# generic_midi_2.net
KiCad netlist of a schematic drawn in EAGLE
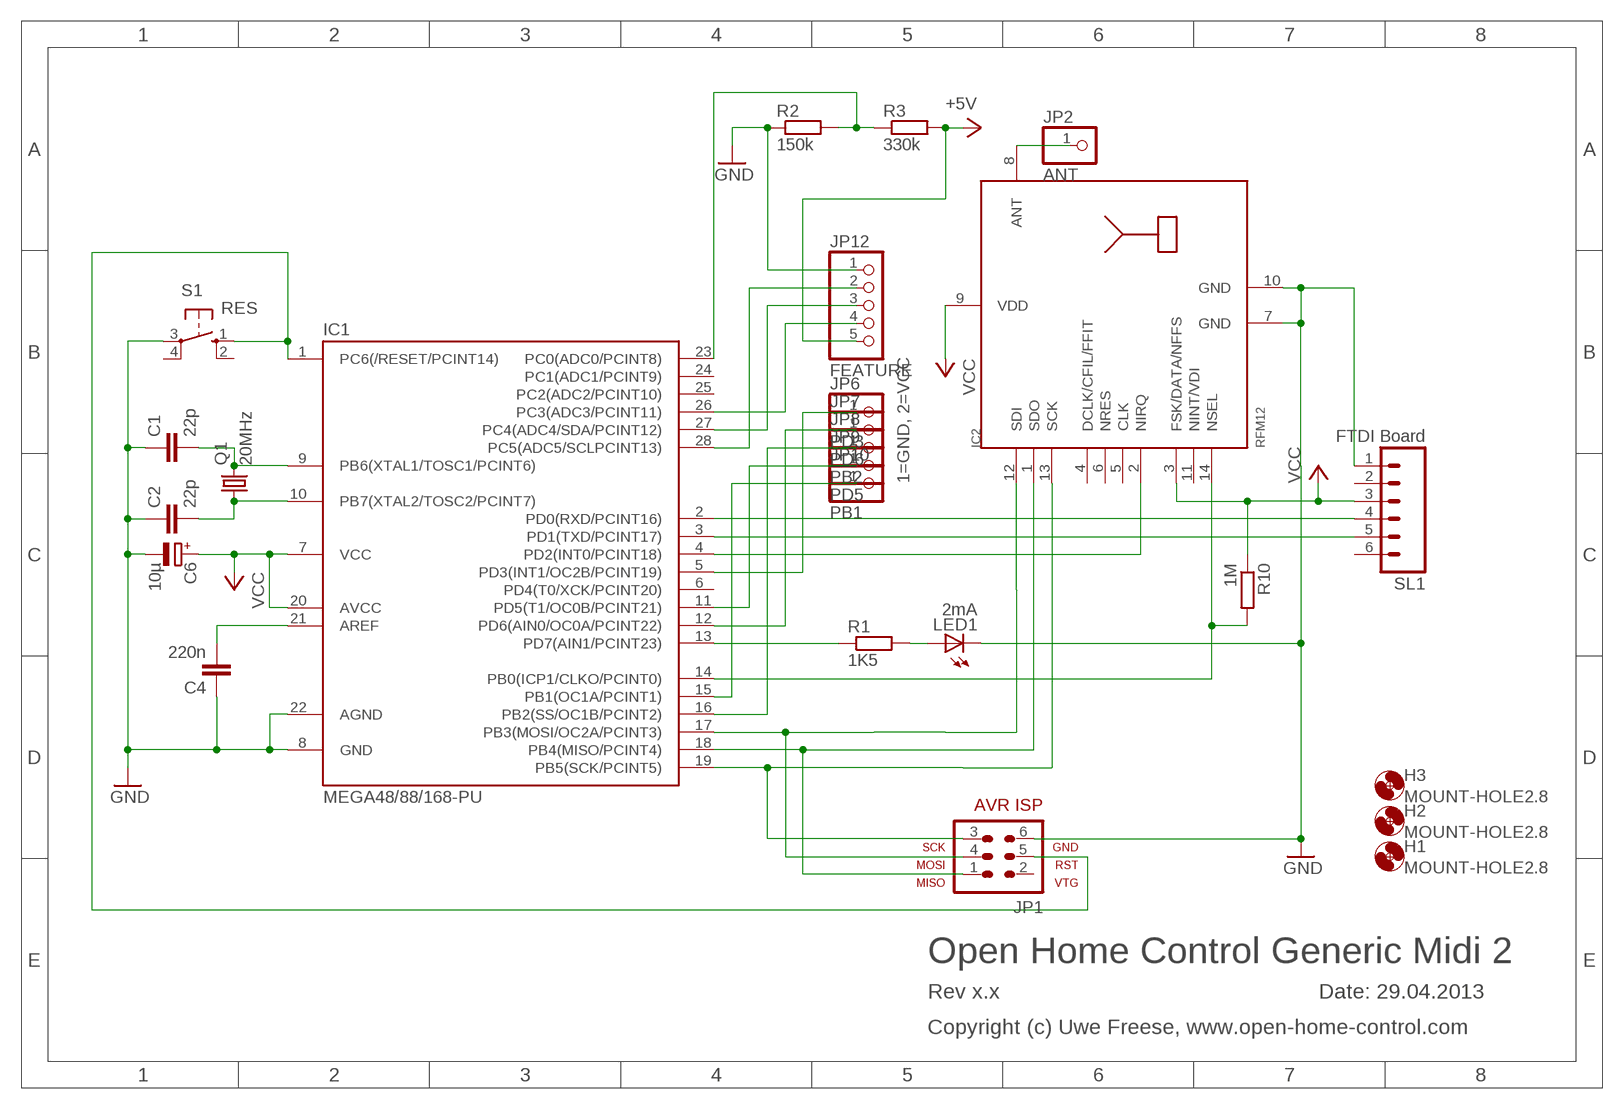
[diagram p0: schematic, sheet 1]

(export (version "E")
  (design (tool "Eeschema 10.0.6"))
  (components
    (comp (ref "C1")
      (value "22p")
      (footprint "eagle-import:C025-024X044")
      (libsource (lib "eagle-import") (part "C-EU025-024X044"))
    )
    (comp (ref "C2")
      (value "22p")
      (footprint "eagle-import:C025-024X044")
      (libsource (lib "eagle-import") (part "C-EU025-024X044"))
    )
    (comp (ref "C4")
      (value "220n")
      (footprint "eagle-import:C025-030X050")
      (libsource (lib "eagle-import") (part "C-EU025-030X050"))
    )
    (comp (ref "C6")
      (value "10µ")
      (footprint "eagle-import:E1,8-4")
      (libsource (lib "eagle-import") (part "CPOL-EUE1.8-4"))
    )
    (comp (ref "H1")
      (value "MOUNT-HOLE2.8")
      (footprint "eagle-import:2,8")
      (libsource (lib "eagle-import") (part "MOUNT-HOLE2.8"))
    )
    (comp (ref "H2")
      (value "MOUNT-HOLE2.8")
      (footprint "eagle-import:2,8")
      (libsource (lib "eagle-import") (part "MOUNT-HOLE2.8"))
    )
    (comp (ref "H3")
      (value "MOUNT-HOLE2.8")
      (footprint "eagle-import:2,8")
      (libsource (lib "eagle-import") (part "MOUNT-HOLE2.8"))
    )
    (comp (ref "IC1")
      (value "MEGA48/88/168-PU")
      (footprint "eagle-import:DIL28-3")
      (libsource (lib "eagle-import") (part "MEGA48/88/168-PU"))
    )
    (comp (ref "IC2")
      (value "RFM12")
      (footprint "eagle-import:RFM")
      (libsource (lib "eagle-import") (part "RFM12"))
    )
    (comp (ref "JP1")
      (value "AVR-ISP-6")
      (footprint "eagle-import:AVR-ISP-6")
      (libsource (lib "eagle-import") (part "AVR-ISP-6"))
    )
    (comp (ref "JP2")
      (value "ANT")
      (footprint "eagle-import:1X01")
      (libsource (lib "eagle-import") (part "PINHD-1X1"))
    )
    (comp (ref "JP6")
      (value "PD3")
      (footprint "eagle-import:1X01")
      (libsource (lib "eagle-import") (part "PINHD-1X1"))
    )
    (comp (ref "JP7")
      (value "PD6")
      (footprint "eagle-import:1X01")
      (libsource (lib "eagle-import") (part "PINHD-1X1"))
    )
    (comp (ref "JP8")
      (value "PB2")
      (footprint "eagle-import:1X01")
      (libsource (lib "eagle-import") (part "PINHD-1X1"))
    )
    (comp (ref "JP9")
      (value "PD5")
      (footprint "eagle-import:1X01")
      (libsource (lib "eagle-import") (part "PINHD-1X1"))
    )
    (comp (ref "JP10")
      (value "PB1")
      (footprint "eagle-import:1X01")
      (libsource (lib "eagle-import") (part "PINHD-1X1"))
    )
    (comp (ref "JP12")
      (value "FEATURE")
      (footprint "eagle-import:1X05")
      (libsource (lib "eagle-import") (part "PINHD-1X5"))
    )
    (comp (ref "LED1")
      (value "2mA")
      (footprint "eagle-import:LED3MM")
      (libsource (lib "eagle-import") (part "LED3MM"))
    )
    (comp (ref "Q1")
      (value "20MHz")
      (footprint "eagle-import:HC49_S")
      (libsource (lib "eagle-import") (part "CRYSTALHC49S"))
    )
    (comp (ref "R1")
      (value "1K5")
      (footprint "eagle-import:0207_7")
      (libsource (lib "eagle-import") (part "R-EU_0207/7"))
    )
    (comp (ref "R2")
      (value "150k")
      (footprint "eagle-import:0207_7")
      (libsource (lib "eagle-import") (part "R-EU_0207/7"))
    )
    (comp (ref "R3")
      (value "330k")
      (footprint "eagle-import:0207_7")
      (libsource (lib "eagle-import") (part "R-EU_0207/7"))
    )
    (comp (ref "R10")
      (value "1M")
      (footprint "eagle-import:0207_7")
      (libsource (lib "eagle-import") (part "R-EU_0207/7"))
    )
    (comp (ref "S1")
      (value "RES")
      (footprint "eagle-import:B3F-10XX")
      (fields (field (name "MPN") "B3F-1000"))
      (libsource (lib "eagle-import") (part "10-XX"))
    )
    (comp (ref "SL1")
      (value "FTDI Board")
      (footprint "eagle-import:06P")
      (libsource (lib "eagle-import") (part "M06"))
    )
  )
  (nets
    (net (code "1") (name "+5V") (class "Default")
      (node (ref "JP12") (pin "5") (pinfunction "5_5") (pintype "passive"))
      (node (ref "R3") (pin "2") (pinfunction "2_2") (pintype "passive"))
    )
    (net (code "2") (name "GND") (class "Default")
      (node (ref "C1") (pin "1") (pinfunction "1_1") (pintype "passive"))
      (node (ref "C2") (pin "1") (pinfunction "1_1") (pintype "passive"))
      (node (ref "C4") (pin "1") (pinfunction "1_1") (pintype "passive"))
      (node (ref "C6") (pin "-") (pinfunction "-_-") (pintype "passive"))
      (node (ref "IC1") (pin "22") (pinfunction "AGND_22") (pintype "power_in"))
      (node (ref "IC1") (pin "8") (pinfunction "GND_8") (pintype "power_in"))
      (node (ref "IC2") (pin "10") (pinfunction "GND_10") (pintype "power_in"))
      (node (ref "IC2") (pin "7") (pinfunction "GND_7") (pintype "power_in"))
      (node (ref "JP1") (pin "6") (pinfunction "6_6") (pintype "passive"))
      (node (ref "JP12") (pin "1") (pinfunction "1_1") (pintype "passive"))
      (node (ref "LED1") (pin "K") (pinfunction "C_K") (pintype "passive"))
      (node (ref "R2") (pin "1") (pinfunction "1_1") (pintype "passive"))
      (node (ref "S1") (pin "3") (pinfunction "P_3") (pintype "passive"))
      (node (ref "SL1") (pin "1") (pinfunction "1_1") (pintype "passive"))
    )
    (net (code "3") (name "Net-(IC1-AREF)") (class "Default")
      (node (ref "C4") (pin "2") (pinfunction "2_2") (pintype "passive"))
      (node (ref "IC1") (pin "21") (pinfunction "AREF_21") (pintype "passive"))
    )
    (net (code "4") (name "Net-(IC1-PB0(ICP1{slash}CLKO{slash}PCINT0))") (class "Default")
      (node (ref "IC1") (pin "14") (pinfunction "PB0(ICP1/CLKO/PCINT0)_14") (pintype "bidirectional"))
      (node (ref "IC2") (pin "14") (pinfunction "NSEL_14") (pintype "bidirectional"))
      (node (ref "R10") (pin "2") (pinfunction "2_2") (pintype "passive"))
    )
    (net (code "5") (name "Net-(IC1-PB1(OC1A{slash}PCINT1))") (class "Default")
      (node (ref "IC1") (pin "15") (pinfunction "PB1(OC1A/PCINT1)_15") (pintype "bidirectional"))
      (node (ref "JP10") (pin "1") (pinfunction "1_1") (pintype "passive"))
    )
    (net (code "6") (name "Net-(IC1-PB2(SS{slash}OC1B{slash}PCINT2))") (class "Default")
      (node (ref "IC1") (pin "16") (pinfunction "PB2(SS/OC1B/PCINT2)_16") (pintype "bidirectional"))
      (node (ref "JP8") (pin "1") (pinfunction "1_1") (pintype "passive"))
    )
    (net (code "7") (name "Net-(IC1-PB3(MOSI{slash}OC2A{slash}PCINT3))") (class "Default")
      (node (ref "IC1") (pin "17") (pinfunction "PB3(MOSI/OC2A/PCINT3)_17") (pintype "bidirectional"))
      (node (ref "IC2") (pin "12") (pinfunction "SDI_12") (pintype "bidirectional"))
      (node (ref "JP1") (pin "4") (pinfunction "4_4") (pintype "passive"))
    )
    (net (code "8") (name "Net-(IC1-PB4(MISO{slash}PCINT4))") (class "Default")
      (node (ref "IC1") (pin "18") (pinfunction "PB4(MISO/PCINT4)_18") (pintype "bidirectional"))
      (node (ref "IC2") (pin "1") (pinfunction "SDO_1") (pintype "bidirectional"))
      (node (ref "JP1") (pin "1") (pinfunction "1_1") (pintype "passive"))
    )
    (net (code "9") (name "Net-(IC1-PB5(SCK{slash}PCINT5))") (class "Default")
      (node (ref "IC1") (pin "19") (pinfunction "PB5(SCK/PCINT5)_19") (pintype "bidirectional"))
      (node (ref "IC2") (pin "13") (pinfunction "SCK_13") (pintype "bidirectional"))
      (node (ref "JP1") (pin "3") (pinfunction "3_3") (pintype "passive"))
    )
    (net (code "10") (name "Net-(IC1-PB6(XTAL1{slash}TOSC1{slash}PCINT6))") (class "Default")
      (node (ref "C1") (pin "2") (pinfunction "2_2") (pintype "passive"))
      (node (ref "IC1") (pin "9") (pinfunction "PB6(XTAL1/TOSC1/PCINT6)_9") (pintype "bidirectional"))
      (node (ref "Q1") (pin "2") (pinfunction "2_2") (pintype "passive"))
    )
    (net (code "11") (name "Net-(IC1-PB7(XTAL2{slash}TOSC2{slash}PCINT7))") (class "Default")
      (node (ref "C2") (pin "2") (pinfunction "2_2") (pintype "passive"))
      (node (ref "IC1") (pin "10") (pinfunction "PB7(XTAL2/TOSC2/PCINT7)_10") (pintype "bidirectional"))
      (node (ref "Q1") (pin "1") (pinfunction "1_1") (pintype "passive"))
    )
    (net (code "12") (name "Net-(IC1-PC0(ADC0{slash}PCINT8))") (class "Default")
      (node (ref "IC1") (pin "23") (pinfunction "PC0(ADC0/PCINT8)_23") (pintype "bidirectional"))
      (node (ref "R2") (pin "2") (pinfunction "2_2") (pintype "passive"))
      (node (ref "R3") (pin "1") (pinfunction "1_1") (pintype "passive"))
    )
    (net (code "13") (name "Net-(IC1-PC3(ADC3{slash}PCINT11))") (class "Default")
      (node (ref "IC1") (pin "26") (pinfunction "PC3(ADC3/PCINT11)_26") (pintype "bidirectional"))
      (node (ref "JP12") (pin "4") (pinfunction "4_4") (pintype "passive"))
    )
    (net (code "14") (name "Net-(IC1-PC4(ADC4{slash}SDA{slash}PCINT12))") (class "Default")
      (node (ref "IC1") (pin "27") (pinfunction "PC4(ADC4/SDA/PCINT12)_27") (pintype "bidirectional"))
      (node (ref "JP12") (pin "3") (pinfunction "3_3") (pintype "passive"))
    )
    (net (code "15") (name "Net-(IC1-PC5(ADC5{slash}SCLPCINT13))") (class "Default")
      (node (ref "IC1") (pin "28") (pinfunction "PC5(ADC5/SCLPCINT13)_28") (pintype "bidirectional"))
      (node (ref "JP12") (pin "2") (pinfunction "2_2") (pintype "passive"))
    )
    (net (code "16") (name "Net-(IC1-PC6({slash}RESET{slash}PCINT14))") (class "Default")
      (node (ref "IC1") (pin "1") (pinfunction "PC6(/RESET/PCINT14)_1") (pintype "bidirectional"))
      (node (ref "JP1") (pin "5") (pinfunction "5_5") (pintype "passive"))
      (node (ref "S1") (pin "1") (pinfunction "S_1") (pintype "passive"))
    )
    (net (code "17") (name "Net-(IC1-PD0(RXD{slash}PCINT16))") (class "Default")
      (node (ref "IC1") (pin "2") (pinfunction "PD0(RXD/PCINT16)_2") (pintype "bidirectional"))
      (node (ref "SL1") (pin "4") (pinfunction "4_4") (pintype "passive"))
    )
    (net (code "18") (name "Net-(IC1-PD1(TXD{slash}PCINT17))") (class "Default")
      (node (ref "IC1") (pin "3") (pinfunction "PD1(TXD/PCINT17)_3") (pintype "bidirectional"))
      (node (ref "SL1") (pin "5") (pinfunction "5_5") (pintype "passive"))
    )
    (net (code "19") (name "Net-(IC1-PD2(INT0{slash}PCINT18))") (class "Default")
      (node (ref "IC1") (pin "4") (pinfunction "PD2(INT0/PCINT18)_4") (pintype "bidirectional"))
      (node (ref "IC2") (pin "2") (pinfunction "NIRQ_2") (pintype "bidirectional"))
    )
    (net (code "20") (name "Net-(IC1-PD3(INT1{slash}OC2B{slash}PCINT19))") (class "Default")
      (node (ref "IC1") (pin "5") (pinfunction "PD3(INT1/OC2B/PCINT19)_5") (pintype "bidirectional"))
      (node (ref "JP6") (pin "1") (pinfunction "1_1") (pintype "passive"))
    )
    (net (code "21") (name "Net-(IC1-PD5(T1{slash}OC0B{slash}PCINT21))") (class "Default")
      (node (ref "IC1") (pin "11") (pinfunction "PD5(T1/OC0B/PCINT21)_11") (pintype "bidirectional"))
      (node (ref "JP9") (pin "1") (pinfunction "1_1") (pintype "passive"))
    )
    (net (code "22") (name "Net-(IC1-PD6(AIN0{slash}OC0A{slash}PCINT22))") (class "Default")
      (node (ref "IC1") (pin "12") (pinfunction "PD6(AIN0/OC0A/PCINT22)_12") (pintype "bidirectional"))
      (node (ref "JP7") (pin "1") (pinfunction "1_1") (pintype "passive"))
    )
    (net (code "23") (name "Net-(IC1-PD7(AIN1{slash}PCINT23))") (class "Default")
      (node (ref "IC1") (pin "13") (pinfunction "PD7(AIN1/PCINT23)_13") (pintype "bidirectional"))
      (node (ref "R1") (pin "1") (pinfunction "1_1") (pintype "passive"))
    )
    (net (code "24") (name "Net-(IC2-ANT)") (class "Default")
      (node (ref "IC2") (pin "8") (pinfunction "ANT_8") (pintype "output"))
      (node (ref "JP2") (pin "1") (pinfunction "1_1") (pintype "passive"))
    )
    (net (code "25") (name "Net-(LED1-PadA)") (class "Default")
      (node (ref "LED1") (pin "A") (pinfunction "A_A") (pintype "passive"))
      (node (ref "R1") (pin "2") (pinfunction "2_2") (pintype "passive"))
    )
    (net (code "26") (name "VCC") (class "Default")
      (node (ref "C6") (pin "+") (pinfunction "+_+") (pintype "passive"))
      (node (ref "IC1") (pin "20") (pinfunction "AVCC_20") (pintype "passive"))
      (node (ref "IC1") (pin "7") (pinfunction "VCC_7") (pintype "power_in"))
      (node (ref "IC2") (pin "3") (pinfunction "FSK/DATA/NFFS_3") (pintype "bidirectional"))
      (node (ref "IC2") (pin "9") (pinfunction "VDD_9") (pintype "power_in"))
      (node (ref "R10") (pin "1") (pinfunction "1_1") (pintype "passive"))
      (node (ref "SL1") (pin "3") (pinfunction "3_3") (pintype "passive"))
    )
    (net (code "27") (name "unconnected-(IC1-PC1(ADC1{slash}PCINT9)-Pad24)") (class "Default")
      (node (ref "IC1") (pin "24") (pinfunction "PC1(ADC1/PCINT9)_24") (pintype "bidirectional"))
    )
    (net (code "28") (name "unconnected-(IC1-PC2(ADC2{slash}PCINT10)-Pad25)") (class "Default")
      (node (ref "IC1") (pin "25") (pinfunction "PC2(ADC2/PCINT10)_25") (pintype "bidirectional"))
    )
    (net (code "29") (name "unconnected-(IC1-PD4(T0{slash}XCK{slash}PCINT20)-Pad6)") (class "Default")
      (node (ref "IC1") (pin "6") (pinfunction "PD4(T0/XCK/PCINT20)_6") (pintype "bidirectional"))
    )
    (net (code "30") (name "unconnected-(IC2-CLK-Pad5)") (class "Default")
      (node (ref "IC2") (pin "5") (pinfunction "CLK_5") (pintype "bidirectional"))
    )
    (net (code "31") (name "unconnected-(IC2-DCLK{slash}CFIL{slash}FFIT-Pad4)") (class "Default")
      (node (ref "IC2") (pin "4") (pinfunction "DCLK/CFIL/FFIT_4") (pintype "bidirectional"))
    )
    (net (code "32") (name "unconnected-(IC2-NINT{slash}VDI-Pad11)") (class "Default")
      (node (ref "IC2") (pin "11") (pinfunction "NINT/VDI_11") (pintype "bidirectional"))
    )
    (net (code "33") (name "unconnected-(IC2-NRES-Pad6)") (class "Default")
      (node (ref "IC2") (pin "6") (pinfunction "NRES_6") (pintype "bidirectional"))
    )
    (net (code "34") (name "unconnected-(JP1-Pad2)") (class "Default")
      (node (ref "JP1") (pin "2") (pinfunction "2_2") (pintype "passive"))
    )
    (net (code "35") (name "unconnected-(S1-P1-Pad4)") (class "Default")
      (node (ref "S1") (pin "4") (pinfunction "P1_4") (pintype "passive"))
    )
    (net (code "36") (name "unconnected-(S1-S1-Pad2)") (class "Default")
      (node (ref "S1") (pin "2") (pinfunction "S1_2") (pintype "passive"))
    )
    (net (code "37") (name "unconnected-(SL1-Pad2)") (class "Default")
      (node (ref "SL1") (pin "2") (pinfunction "2_2") (pintype "passive"))
    )
    (net (code "38") (name "unconnected-(SL1-Pad6)") (class "Default")
      (node (ref "SL1") (pin "6") (pinfunction "6_6") (pintype "passive"))
    )
  )
)
